# Keg_Cop_-_Devel_SMD.net
KiCad netlist of a schematic drawn in EAGLE
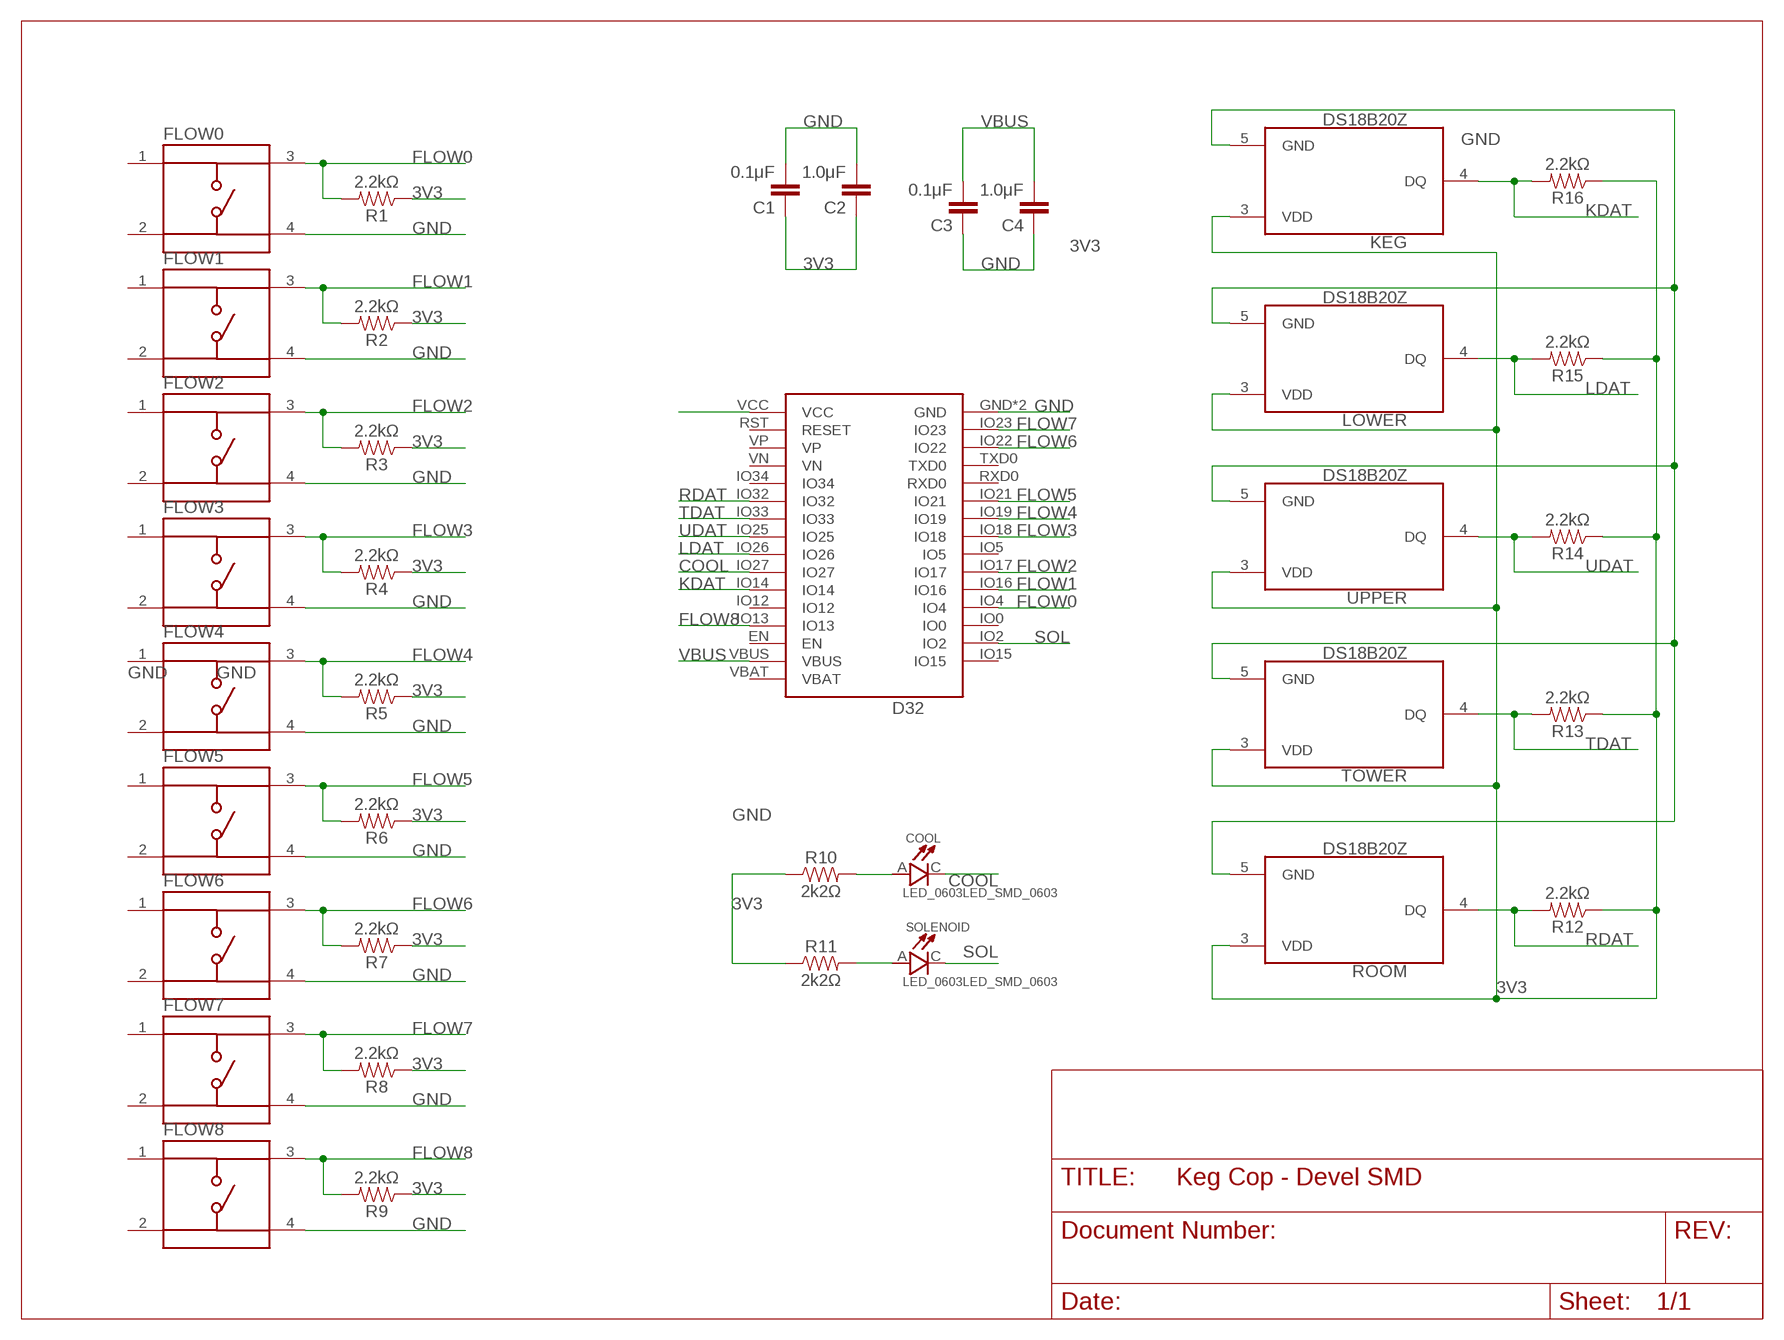
[diagram p0: schematic, sheet 1]

(export (version "E")
  (design (tool "Eeschema 10.0.6"))
  (components
    (comp (ref "C1")
      (value "0.1μF")
      (footprint "eagle-import:SMD-0805")
      (libsource (lib "eagle-import") (part "CAP_SMD0805"))
    )
    (comp (ref "C2")
      (value "1.0μF")
      (footprint "eagle-import:SMD-0805")
      (libsource (lib "eagle-import") (part "CAP_SMD0805"))
    )
    (comp (ref "C3")
      (value "0.1μF")
      (footprint "eagle-import:SMD-0805")
      (libsource (lib "eagle-import") (part "CAP_SMD0805"))
    )
    (comp (ref "C4")
      (value "1.0μF")
      (footprint "eagle-import:SMD-0805")
      (libsource (lib "eagle-import") (part "CAP_SMD0805"))
    )
    (comp (ref "COOL")
      (value "LED_0603LED_SMD_0603")
      (footprint "eagle-import:LED_SMD_0603")
      (fields (field (name "LCSC_PART") "C2286"))
      (libsource (lib "eagle-import") (part "LED_0603LED_SMD_0603"))
    )
    (comp (ref "D32")
      (value "Lolin D32")
      (footprint "eagle-import:D32_NO_BATT")
      (fields (field (name "SPICEPREFIX") "X"))
      (libsource (lib "eagle-import") (part "WEMOS-D32D32_NO_BATT"))
    )
    (comp (ref "FLOW0")
      (value "TS08-66-43-BK-160-SMT-67")
      (footprint "eagle-import:SW_TS08-66-43-BK-160-SMT-67")
      (fields
        (field (name "LCSC_PART") "C2888744")
        (field (name "MF") "BZCN")
        (field (name "MP") "TSD003B04326A03")
      )
      (libsource (lib "eagle-import") (part "TS08-66-43-BK-160-SMT-67"))
    )
    (comp (ref "FLOW1")
      (value "TS08-66-43-BK-160-SMT-67")
      (footprint "eagle-import:SW_TS08-66-43-BK-160-SMT-67")
      (fields
        (field (name "LCSC_PART") "C2888744")
        (field (name "MF") "BZCN")
        (field (name "MP") "TSD003B04326A03")
      )
      (libsource (lib "eagle-import") (part "TS08-66-43-BK-160-SMT-67"))
    )
    (comp (ref "FLOW2")
      (value "TS08-66-43-BK-160-SMT-67")
      (footprint "eagle-import:SW_TS08-66-43-BK-160-SMT-67")
      (fields
        (field (name "LCSC_PART") "C2888744")
        (field (name "MF") "BZCN")
        (field (name "MP") "TSD003B04326A03")
      )
      (libsource (lib "eagle-import") (part "TS08-66-43-BK-160-SMT-67"))
    )
    (comp (ref "FLOW3")
      (value "TS08-66-43-BK-160-SMT-67")
      (footprint "eagle-import:SW_TS08-66-43-BK-160-SMT-67")
      (fields
        (field (name "LCSC_PART") "C2888744")
        (field (name "MF") "BZCN")
        (field (name "MP") "TSD003B04326A03")
      )
      (libsource (lib "eagle-import") (part "TS08-66-43-BK-160-SMT-67"))
    )
    (comp (ref "FLOW4")
      (value "TS08-66-43-BK-160-SMT-67")
      (footprint "eagle-import:SW_TS08-66-43-BK-160-SMT-67")
      (fields
        (field (name "LCSC_PART") "C2888744")
        (field (name "MF") "BZCN")
        (field (name "MP") "TSD003B04326A03")
      )
      (libsource (lib "eagle-import") (part "TS08-66-43-BK-160-SMT-67"))
    )
    (comp (ref "FLOW5")
      (value "TS08-66-43-BK-160-SMT-67")
      (footprint "eagle-import:SW_TS08-66-43-BK-160-SMT-67")
      (fields
        (field (name "LCSC_PART") "C2888744")
        (field (name "MF") "BZCN")
        (field (name "MP") "TSD003B04326A03")
      )
      (libsource (lib "eagle-import") (part "TS08-66-43-BK-160-SMT-67"))
    )
    (comp (ref "FLOW6")
      (value "TS08-66-43-BK-160-SMT-67")
      (footprint "eagle-import:SW_TS08-66-43-BK-160-SMT-67")
      (fields
        (field (name "LCSC_PART") "C2888744")
        (field (name "MF") "BZCN")
        (field (name "MP") "TSD003B04326A03")
      )
      (libsource (lib "eagle-import") (part "TS08-66-43-BK-160-SMT-67"))
    )
    (comp (ref "FLOW7")
      (value "TS08-66-43-BK-160-SMT-67")
      (footprint "eagle-import:SW_TS08-66-43-BK-160-SMT-67")
      (fields
        (field (name "LCSC_PART") "C2888744")
        (field (name "MF") "BZCN")
        (field (name "MP") "TSD003B04326A03")
      )
      (libsource (lib "eagle-import") (part "TS08-66-43-BK-160-SMT-67"))
    )
    (comp (ref "FLOW8")
      (value "TS08-66-43-BK-160-SMT-67")
      (footprint "eagle-import:SW_TS08-66-43-BK-160-SMT-67")
      (fields
        (field (name "LCSC_PART") "C2888744")
        (field (name "MF") "BZCN")
        (field (name "MP") "TSD003B04326A03")
      )
      (libsource (lib "eagle-import") (part "TS08-66-43-BK-160-SMT-67"))
    )
    (comp (ref "KEG")
      (value "DS18B20Z")
      (footprint "eagle-import:SOIC127P600X175-8N")
      (fields (field (name "LCSC_PART") "C695837") (field (name "MF") "Maxim Integrated"))
      (libsource (lib "eagle-import") (part "DS18B20Z"))
    )
    (comp (ref "LOWER")
      (value "DS18B20Z")
      (footprint "eagle-import:SOIC127P600X175-8N")
      (fields (field (name "LCSC_PART") "C695837") (field (name "MF") "Maxim Integrated"))
      (libsource (lib "eagle-import") (part "DS18B20Z"))
    )
    (comp (ref "R1")
      (value "2.2kΩ")
      (footprint "eagle-import:SMD-0805")
      (libsource (lib "eagle-import") (part "RES_SMD0805"))
    )
    (comp (ref "R2")
      (value "2.2kΩ")
      (footprint "eagle-import:SMD-0805")
      (libsource (lib "eagle-import") (part "RES_SMD0805"))
    )
    (comp (ref "R3")
      (value "2.2kΩ")
      (footprint "eagle-import:SMD-0805")
      (libsource (lib "eagle-import") (part "RES_SMD0805"))
    )
    (comp (ref "R4")
      (value "2.2kΩ")
      (footprint "eagle-import:SMD-0805")
      (libsource (lib "eagle-import") (part "RES_SMD0805"))
    )
    (comp (ref "R5")
      (value "2.2kΩ")
      (footprint "eagle-import:SMD-0805")
      (libsource (lib "eagle-import") (part "RES_SMD0805"))
    )
    (comp (ref "R6")
      (value "2.2kΩ")
      (footprint "eagle-import:SMD-0805")
      (libsource (lib "eagle-import") (part "RES_SMD0805"))
    )
    (comp (ref "R7")
      (value "2.2kΩ")
      (footprint "eagle-import:SMD-0805")
      (libsource (lib "eagle-import") (part "RES_SMD0805"))
    )
    (comp (ref "R8")
      (value "2.2kΩ")
      (footprint "eagle-import:SMD-0805")
      (libsource (lib "eagle-import") (part "RES_SMD0805"))
    )
    (comp (ref "R9")
      (value "2.2kΩ")
      (footprint "eagle-import:SMD-0805")
      (libsource (lib "eagle-import") (part "RES_SMD0805"))
    )
    (comp (ref "R10")
      (value "2k2Ω")
      (footprint "eagle-import:SMD-0805")
      (libsource (lib "eagle-import") (part "RES_SMD0805"))
    )
    (comp (ref "R11")
      (value "2k2Ω")
      (footprint "eagle-import:SMD-0805")
      (libsource (lib "eagle-import") (part "RES_SMD0805"))
    )
    (comp (ref "R12")
      (value "2.2kΩ")
      (footprint "eagle-import:SMD-0805")
      (libsource (lib "eagle-import") (part "RES_SMD0805"))
    )
    (comp (ref "R13")
      (value "2.2kΩ")
      (footprint "eagle-import:SMD-0805")
      (libsource (lib "eagle-import") (part "RES_SMD0805"))
    )
    (comp (ref "R14")
      (value "2.2kΩ")
      (footprint "eagle-import:SMD-0805")
      (libsource (lib "eagle-import") (part "RES_SMD0805"))
    )
    (comp (ref "R15")
      (value "2.2kΩ")
      (footprint "eagle-import:SMD-0805")
      (libsource (lib "eagle-import") (part "RES_SMD0805"))
    )
    (comp (ref "R16")
      (value "2.2kΩ")
      (footprint "eagle-import:SMD-0805")
      (libsource (lib "eagle-import") (part "RES_SMD0805"))
    )
    (comp (ref "ROOM")
      (value "DS18B20Z")
      (footprint "eagle-import:SOIC127P600X175-8N")
      (fields (field (name "LCSC_PART") "C695837") (field (name "MF") "Maxim Integrated"))
      (libsource (lib "eagle-import") (part "DS18B20Z"))
    )
    (comp (ref "SOLENOID")
      (value "LED_0603LED_SMD_0603")
      (footprint "eagle-import:LED_SMD_0603")
      (fields (field (name "LCSC_PART") "C2286"))
      (libsource (lib "eagle-import") (part "LED_0603LED_SMD_0603"))
    )
    (comp (ref "TOWER")
      (value "DS18B20Z")
      (footprint "eagle-import:SOIC127P600X175-8N")
      (fields (field (name "LCSC_PART") "C695837") (field (name "MF") "Maxim Integrated"))
      (libsource (lib "eagle-import") (part "DS18B20Z"))
    )
    (comp (ref "UPPER")
      (value "DS18B20Z")
      (footprint "eagle-import:SOIC127P600X175-8N")
      (fields (field (name "LCSC_PART") "C695837") (field (name "MF") "Maxim Integrated"))
      (libsource (lib "eagle-import") (part "DS18B20Z"))
    )
  )
  (nets
    (net (code "1") (name "/3V3") (class "Default")
      (node (ref "C1") (pin "1") (pinfunction "1_1") (pintype "passive"))
      (node (ref "C2") (pin "1") (pinfunction "1_1") (pintype "passive"))
      (node (ref "D32") (pin "VCC") (pinfunction "VCC_VCC") (pintype "power_in"))
      (node (ref "KEG") (pin "3") (pinfunction "VDD_3") (pintype "power_in"))
      (node (ref "LOWER") (pin "3") (pinfunction "VDD_3") (pintype "power_in"))
      (node (ref "R1") (pin "1") (pinfunction "1_1") (pintype "passive"))
      (node (ref "R10") (pin "1") (pinfunction "1_1") (pintype "passive"))
      (node (ref "R11") (pin "1") (pinfunction "1_1") (pintype "passive"))
      (node (ref "R12") (pin "1") (pinfunction "1_1") (pintype "passive"))
      (node (ref "R13") (pin "1") (pinfunction "1_1") (pintype "passive"))
      (node (ref "R14") (pin "1") (pinfunction "1_1") (pintype "passive"))
      (node (ref "R15") (pin "1") (pinfunction "1_1") (pintype "passive"))
      (node (ref "R16") (pin "1") (pinfunction "1_1") (pintype "passive"))
      (node (ref "R2") (pin "1") (pinfunction "1_1") (pintype "passive"))
      (node (ref "R3") (pin "1") (pinfunction "1_1") (pintype "passive"))
      (node (ref "R4") (pin "1") (pinfunction "1_1") (pintype "passive"))
      (node (ref "R5") (pin "1") (pinfunction "1_1") (pintype "passive"))
      (node (ref "R6") (pin "1") (pinfunction "1_1") (pintype "passive"))
      (node (ref "R7") (pin "1") (pinfunction "1_1") (pintype "passive"))
      (node (ref "R8") (pin "1") (pinfunction "1_1") (pintype "passive"))
      (node (ref "R9") (pin "1") (pinfunction "1_1") (pintype "passive"))
      (node (ref "ROOM") (pin "3") (pinfunction "VDD_3") (pintype "power_in"))
      (node (ref "TOWER") (pin "3") (pinfunction "VDD_3") (pintype "power_in"))
      (node (ref "UPPER") (pin "3") (pinfunction "VDD_3") (pintype "power_in"))
    )
    (net (code "2") (name "/COOL") (class "Default")
      (node (ref "COOL") (pin "C") (pinfunction "C_C") (pintype "passive"))
      (node (ref "D32") (pin "IO27") (pinfunction "IO27_IO27") (pintype "bidirectional"))
    )
    (net (code "3") (name "/FLOW0") (class "Default")
      (node (ref "D32") (pin "IO4") (pinfunction "IO4_IO4") (pintype "bidirectional"))
      (node (ref "FLOW0") (pin "3") (pinfunction "3_3") (pintype "passive"))
      (node (ref "R1") (pin "2") (pinfunction "2_2") (pintype "passive"))
    )
    (net (code "4") (name "/FLOW1") (class "Default")
      (node (ref "D32") (pin "IO16") (pinfunction "IO16_IO16") (pintype "bidirectional"))
      (node (ref "FLOW1") (pin "3") (pinfunction "3_3") (pintype "passive"))
      (node (ref "R2") (pin "2") (pinfunction "2_2") (pintype "passive"))
    )
    (net (code "5") (name "/FLOW2") (class "Default")
      (node (ref "D32") (pin "IO17") (pinfunction "IO17_IO17") (pintype "bidirectional"))
      (node (ref "FLOW2") (pin "3") (pinfunction "3_3") (pintype "passive"))
      (node (ref "R3") (pin "2") (pinfunction "2_2") (pintype "passive"))
    )
    (net (code "6") (name "/FLOW3") (class "Default")
      (node (ref "D32") (pin "IO18") (pinfunction "IO18_IO18") (pintype "bidirectional"))
      (node (ref "FLOW3") (pin "3") (pinfunction "3_3") (pintype "passive"))
      (node (ref "R4") (pin "2") (pinfunction "2_2") (pintype "passive"))
    )
    (net (code "7") (name "/FLOW4") (class "Default")
      (node (ref "D32") (pin "IO19") (pinfunction "IO19_IO19") (pintype "bidirectional"))
      (node (ref "FLOW4") (pin "3") (pinfunction "3_3") (pintype "passive"))
      (node (ref "R5") (pin "2") (pinfunction "2_2") (pintype "passive"))
    )
    (net (code "8") (name "/FLOW5") (class "Default")
      (node (ref "D32") (pin "IO21") (pinfunction "IO21_IO21") (pintype "bidirectional"))
      (node (ref "FLOW5") (pin "3") (pinfunction "3_3") (pintype "passive"))
      (node (ref "R6") (pin "2") (pinfunction "2_2") (pintype "passive"))
    )
    (net (code "9") (name "/FLOW6") (class "Default")
      (node (ref "D32") (pin "IO22") (pinfunction "IO22_IO22") (pintype "bidirectional"))
      (node (ref "FLOW6") (pin "3") (pinfunction "3_3") (pintype "passive"))
      (node (ref "R7") (pin "2") (pinfunction "2_2") (pintype "passive"))
    )
    (net (code "10") (name "/FLOW7") (class "Default")
      (node (ref "D32") (pin "IO23") (pinfunction "IO23_IO23") (pintype "bidirectional"))
      (node (ref "FLOW7") (pin "3") (pinfunction "3_3") (pintype "passive"))
      (node (ref "R8") (pin "2") (pinfunction "2_2") (pintype "passive"))
    )
    (net (code "11") (name "/FLOW8") (class "Default")
      (node (ref "D32") (pin "IO13") (pinfunction "IO13_IO13") (pintype "bidirectional"))
      (node (ref "FLOW8") (pin "3") (pinfunction "3_3") (pintype "passive"))
      (node (ref "R9") (pin "2") (pinfunction "2_2") (pintype "passive"))
    )
    (net (code "12") (name "/GND") (class "Default")
      (node (ref "C1") (pin "2") (pinfunction "2_2") (pintype "passive"))
      (node (ref "C2") (pin "2") (pinfunction "2_2") (pintype "passive"))
      (node (ref "C3") (pin "1") (pinfunction "1_1") (pintype "passive"))
      (node (ref "C4") (pin "1") (pinfunction "1_1") (pintype "passive"))
      (node (ref "D32") (pin "GND") (pinfunction "GND_GND") (pintype "power_in"))
      (node (ref "D32") (pin "GND2") (pinfunction "GND_GND2") (pintype "power_in"))
      (node (ref "FLOW0") (pin "4") (pinfunction "4_4") (pintype "passive"))
      (node (ref "FLOW1") (pin "4") (pinfunction "4_4") (pintype "passive"))
      (node (ref "FLOW2") (pin "4") (pinfunction "4_4") (pintype "passive"))
      (node (ref "FLOW3") (pin "4") (pinfunction "4_4") (pintype "passive"))
      (node (ref "FLOW4") (pin "4") (pinfunction "4_4") (pintype "passive"))
      (node (ref "FLOW5") (pin "4") (pinfunction "4_4") (pintype "passive"))
      (node (ref "FLOW6") (pin "4") (pinfunction "4_4") (pintype "passive"))
      (node (ref "FLOW7") (pin "4") (pinfunction "4_4") (pintype "passive"))
      (node (ref "FLOW8") (pin "4") (pinfunction "4_4") (pintype "passive"))
      (node (ref "KEG") (pin "5") (pinfunction "GND_5") (pintype "power_in"))
      (node (ref "LOWER") (pin "5") (pinfunction "GND_5") (pintype "power_in"))
      (node (ref "ROOM") (pin "5") (pinfunction "GND_5") (pintype "power_in"))
      (node (ref "TOWER") (pin "5") (pinfunction "GND_5") (pintype "power_in"))
      (node (ref "UPPER") (pin "5") (pinfunction "GND_5") (pintype "power_in"))
    )
    (net (code "13") (name "/KDAT") (class "Default")
      (node (ref "D32") (pin "IO14") (pinfunction "IO14_IO14") (pintype "bidirectional"))
      (node (ref "KEG") (pin "4") (pinfunction "DQ_4") (pintype "bidirectional"))
      (node (ref "R16") (pin "2") (pinfunction "2_2") (pintype "passive"))
    )
    (net (code "14") (name "/LDAT") (class "Default")
      (node (ref "D32") (pin "IO26") (pinfunction "IO26_IO26") (pintype "bidirectional"))
      (node (ref "LOWER") (pin "4") (pinfunction "DQ_4") (pintype "bidirectional"))
      (node (ref "R15") (pin "2") (pinfunction "2_2") (pintype "passive"))
    )
    (net (code "15") (name "/RDAT") (class "Default")
      (node (ref "D32") (pin "IO32") (pinfunction "IO32_IO32") (pintype "bidirectional"))
      (node (ref "R12") (pin "2") (pinfunction "2_2") (pintype "passive"))
      (node (ref "ROOM") (pin "4") (pinfunction "DQ_4") (pintype "bidirectional"))
    )
    (net (code "16") (name "/SOL") (class "Default")
      (node (ref "D32") (pin "IO2") (pinfunction "IO2_IO2") (pintype "bidirectional"))
      (node (ref "SOLENOID") (pin "C") (pinfunction "C_C") (pintype "passive"))
    )
    (net (code "17") (name "/TDAT") (class "Default")
      (node (ref "D32") (pin "IO33") (pinfunction "IO33_IO33") (pintype "bidirectional"))
      (node (ref "R13") (pin "2") (pinfunction "2_2") (pintype "passive"))
      (node (ref "TOWER") (pin "4") (pinfunction "DQ_4") (pintype "bidirectional"))
    )
    (net (code "18") (name "/UDAT") (class "Default")
      (node (ref "D32") (pin "IO25") (pinfunction "IO25_IO25") (pintype "bidirectional"))
      (node (ref "R14") (pin "2") (pinfunction "2_2") (pintype "passive"))
      (node (ref "UPPER") (pin "4") (pinfunction "DQ_4") (pintype "bidirectional"))
    )
    (net (code "19") (name "/VBUS") (class "Default")
      (node (ref "C3") (pin "2") (pinfunction "2_2") (pintype "passive"))
      (node (ref "C4") (pin "2") (pinfunction "2_2") (pintype "passive"))
      (node (ref "D32") (pin "VBUS") (pinfunction "VBUS_VBUS") (pintype "bidirectional"))
    )
    (net (code "20") (name "Net-(COOL-PadA)") (class "Default")
      (node (ref "COOL") (pin "A") (pinfunction "A_A") (pintype "passive"))
      (node (ref "R10") (pin "2") (pinfunction "2_2") (pintype "passive"))
    )
    (net (code "21") (name "Net-(R11-Pad2)") (class "Default")
      (node (ref "R11") (pin "2") (pinfunction "2_2") (pintype "passive"))
      (node (ref "SOLENOID") (pin "A") (pinfunction "A_A") (pintype "passive"))
    )
    (net (code "22") (name "unconnected-(D32-PadEN)") (class "Default")
      (node (ref "D32") (pin "EN") (pinfunction "EN_EN") (pintype "bidirectional"))
    )
    (net (code "23") (name "unconnected-(D32-PadIO0)") (class "Default")
      (node (ref "D32") (pin "IO0") (pinfunction "IO0_IO0") (pintype "bidirectional"))
    )
    (net (code "24") (name "unconnected-(D32-PadIO5)") (class "Default")
      (node (ref "D32") (pin "IO5") (pinfunction "IO5_IO5") (pintype "bidirectional"))
    )
    (net (code "25") (name "unconnected-(D32-PadIO12)") (class "Default")
      (node (ref "D32") (pin "IO12") (pinfunction "IO12_IO12") (pintype "bidirectional"))
    )
    (net (code "26") (name "unconnected-(D32-PadIO15)") (class "Default")
      (node (ref "D32") (pin "IO15") (pinfunction "IO15_IO15") (pintype "bidirectional"))
    )
    (net (code "27") (name "unconnected-(D32-PadIO34)") (class "Default")
      (node (ref "D32") (pin "IO34") (pinfunction "IO34_IO34") (pintype "bidirectional"))
    )
    (net (code "28") (name "unconnected-(D32-PadRXD0)") (class "Default")
      (node (ref "D32") (pin "RXD0") (pinfunction "RXD0_RXD0") (pintype "input"))
    )
    (net (code "29") (name "unconnected-(D32-PadTXD0)") (class "Default")
      (node (ref "D32") (pin "TXD0") (pinfunction "TXD0_TXD0") (pintype "output"))
    )
    (net (code "30") (name "unconnected-(D32-PadVBAT)") (class "Default")
      (node (ref "D32") (pin "VBAT") (pinfunction "VBAT_VBAT") (pintype "bidirectional"))
    )
    (net (code "31") (name "unconnected-(D32-PadVN)") (class "Default")
      (node (ref "D32") (pin "VN") (pinfunction "VN_VN") (pintype "bidirectional"))
    )
    (net (code "32") (name "unconnected-(D32-PadVP)") (class "Default")
      (node (ref "D32") (pin "VP") (pinfunction "VP_VP") (pintype "bidirectional"))
    )
    (net (code "33") (name "unconnected-(D32-RESET-PadRST)") (class "Default")
      (node (ref "D32") (pin "RST") (pinfunction "RESET_RST") (pintype "bidirectional"))
    )
    (net (code "34") (name "unconnected-(FLOW0-Pad1)") (class "Default")
      (node (ref "FLOW0") (pin "1") (pinfunction "1_1") (pintype "passive"))
    )
    (net (code "35") (name "unconnected-(FLOW0-Pad2)") (class "Default")
      (node (ref "FLOW0") (pin "2") (pinfunction "2_2") (pintype "passive"))
    )
    (net (code "36") (name "unconnected-(FLOW1-Pad1)") (class "Default")
      (node (ref "FLOW1") (pin "1") (pinfunction "1_1") (pintype "passive"))
    )
    (net (code "37") (name "unconnected-(FLOW1-Pad2)") (class "Default")
      (node (ref "FLOW1") (pin "2") (pinfunction "2_2") (pintype "passive"))
    )
    (net (code "38") (name "unconnected-(FLOW2-Pad1)") (class "Default")
      (node (ref "FLOW2") (pin "1") (pinfunction "1_1") (pintype "passive"))
    )
    (net (code "39") (name "unconnected-(FLOW2-Pad2)") (class "Default")
      (node (ref "FLOW2") (pin "2") (pinfunction "2_2") (pintype "passive"))
    )
    (net (code "40") (name "unconnected-(FLOW3-Pad1)") (class "Default")
      (node (ref "FLOW3") (pin "1") (pinfunction "1_1") (pintype "passive"))
    )
    (net (code "41") (name "unconnected-(FLOW3-Pad2)") (class "Default")
      (node (ref "FLOW3") (pin "2") (pinfunction "2_2") (pintype "passive"))
    )
    (net (code "42") (name "unconnected-(FLOW4-Pad1)") (class "Default")
      (node (ref "FLOW4") (pin "1") (pinfunction "1_1") (pintype "passive"))
    )
    (net (code "43") (name "unconnected-(FLOW4-Pad2)") (class "Default")
      (node (ref "FLOW4") (pin "2") (pinfunction "2_2") (pintype "passive"))
    )
    (net (code "44") (name "unconnected-(FLOW5-Pad1)") (class "Default")
      (node (ref "FLOW5") (pin "1") (pinfunction "1_1") (pintype "passive"))
    )
    (net (code "45") (name "unconnected-(FLOW5-Pad2)") (class "Default")
      (node (ref "FLOW5") (pin "2") (pinfunction "2_2") (pintype "passive"))
    )
    (net (code "46") (name "unconnected-(FLOW6-Pad1)") (class "Default")
      (node (ref "FLOW6") (pin "1") (pinfunction "1_1") (pintype "passive"))
    )
    (net (code "47") (name "unconnected-(FLOW6-Pad2)") (class "Default")
      (node (ref "FLOW6") (pin "2") (pinfunction "2_2") (pintype "passive"))
    )
    (net (code "48") (name "unconnected-(FLOW7-Pad1)") (class "Default")
      (node (ref "FLOW7") (pin "1") (pinfunction "1_1") (pintype "passive"))
    )
    (net (code "49") (name "unconnected-(FLOW7-Pad2)") (class "Default")
      (node (ref "FLOW7") (pin "2") (pinfunction "2_2") (pintype "passive"))
    )
    (net (code "50") (name "unconnected-(FLOW8-Pad1)") (class "Default")
      (node (ref "FLOW8") (pin "1") (pinfunction "1_1") (pintype "passive"))
    )
    (net (code "51") (name "unconnected-(FLOW8-Pad2)") (class "Default")
      (node (ref "FLOW8") (pin "2") (pinfunction "2_2") (pintype "passive"))
    )
  )
)
